# CT_v01.net
KiCad netlist of a schematic drawn in Altium Designer
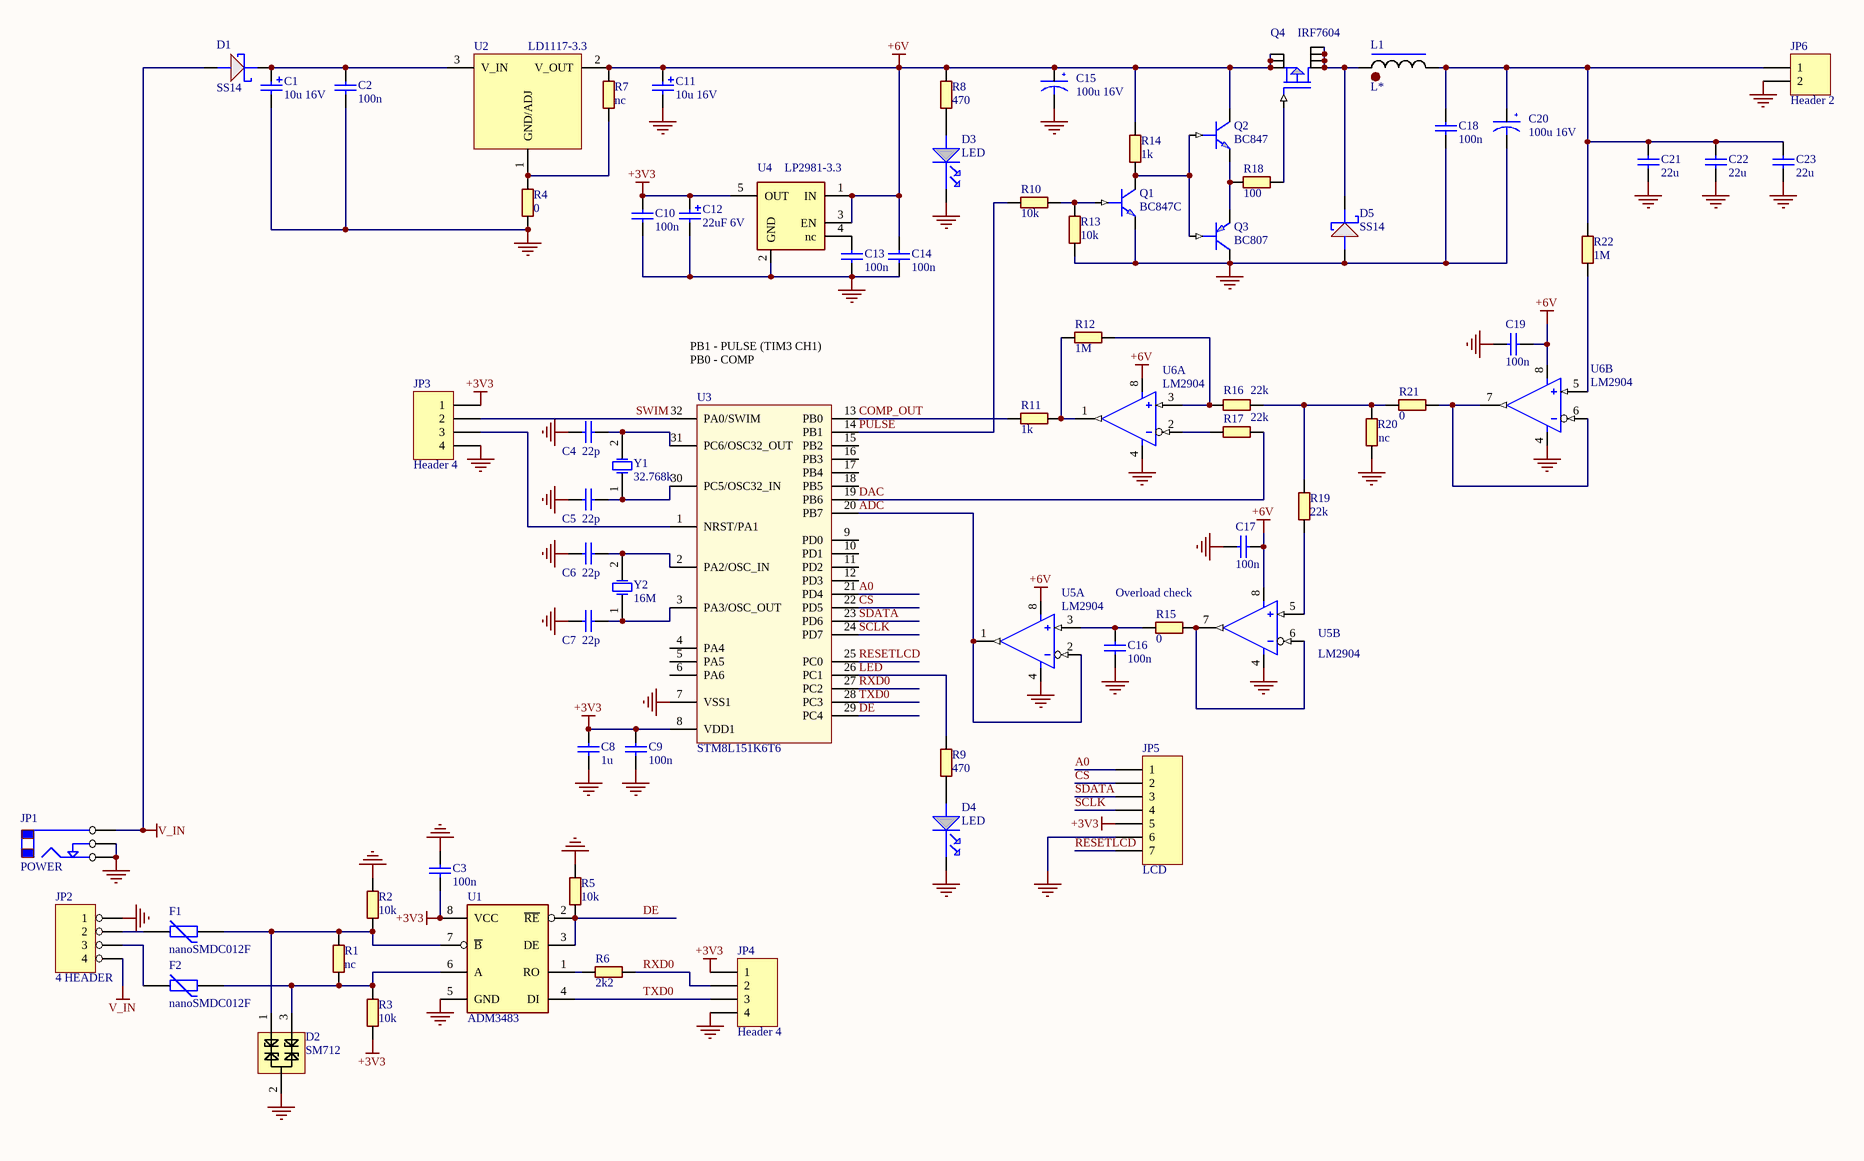
[diagram p0: CT_v01.SchDoc]

(export (version "E")
  (design (tool "Eeschema 10.0.6"))
  (components
    (comp (ref "C1") (value "10u 16V") (footprint "CAPMP3217X18N") (libsource (lib "Discrete") (part "CAPP")))
    (comp (ref "C2") (value "100n") (footprint "CAPC1608X08N") (libsource (lib "Discrete") (part "CAPN")))
    (comp (ref "C3") (value "100n") (footprint "CAPC1608X08N") (libsource (lib "Discrete") (part "CAPN")))
    (comp (ref "C4") (value "22p") (footprint "CAPC1608X08N") (libsource (lib "Discrete") (part "CAPN")))
    (comp (ref "C5") (value "22p") (footprint "CAPC1608X08N") (libsource (lib "Discrete") (part "CAPN")))
    (comp (ref "C6") (value "22p") (footprint "CAPC1608X08N") (libsource (lib "Discrete") (part "CAPN")))
    (comp (ref "C7") (value "22p") (footprint "CAPC1608X08N") (libsource (lib "Discrete") (part "CAPN")))
    (comp (ref "C8") (value "1u") (footprint "CAPC1608X08N") (libsource (lib "Discrete") (part "CAPN")))
    (comp (ref "C9") (value "100n") (footprint "CAPC1608X08N") (libsource (lib "Discrete") (part "CAPN")))
    (comp (ref "C10") (value "100n") (footprint "CAPC1608X08N") (libsource (lib "Discrete") (part "CAPN")))
    (comp (ref "C11")
      (value "10u 16V")
      (footprint "CAPMP3217X18N")
      (libsource (lib "Discrete") (part "CAPP"))
    )
    (comp (ref "C12")
      (value "22uF 6V")
      (footprint "CAPMP3217X18N")
      (libsource (lib "Discrete") (part "CAPP"))
    )
    (comp (ref "C13") (value "100n") (footprint "CAPC1608X08N") (libsource (lib "Discrete") (part "CAPN")))
    (comp (ref "C14") (value "100n") (footprint "CAPC1608X08N") (libsource (lib "Discrete") (part "CAPN")))
    (comp (ref "C15")
      (value "100u 16V")
      (footprint "CAPPRD200W50D600H1250")
      (libsource (lib "Discrete") (part "C-EL-DIP"))
    )
    (comp (ref "C16") (value "100n") (footprint "CAPC1608X08N") (libsource (lib "Discrete") (part "CAPN")))
    (comp (ref "C17") (value "100n") (footprint "CAPC1608X08N") (libsource (lib "Discrete") (part "CAPN")))
    (comp (ref "C18") (value "100n") (footprint "CAPC1608X08N") (libsource (lib "Discrete") (part "CAPN")))
    (comp (ref "C19") (value "100n") (footprint "CAPC1608X08N") (libsource (lib "Discrete") (part "CAPN")))
    (comp (ref "C20")
      (value "100u 16V")
      (footprint "CAPPRD200W50D600H1250")
      (libsource (lib "Discrete") (part "C-EL-DIP"))
    )
    (comp (ref "C21") (value "22u") (footprint "CAPC3216X14N") (libsource (lib "Discrete") (part "CAPN")))
    (comp (ref "C22") (value "22u") (footprint "CAPC3216X14N") (libsource (lib "Discrete") (part "CAPN")))
    (comp (ref "C23") (value "22u") (footprint "CAPC3216X14N") (libsource (lib "Discrete") (part "CAPN")))
    (comp (ref "D1")
      (value "SS14")
      (footprint "DIOM521X260X241L114X145N")
      (libsource (lib "Discrete") (part "DIODE SCHOTTKY"))
    )
    (comp (ref "D2") (value "SM712") (footprint "SOT-23") (libsource (lib "ul2016") (part "SM712")))
    (comp (ref "D3") (value "LED") (footprint "LEDC200X125X80L40N") (libsource (lib "Discrete") (part "LED")))
    (comp (ref "D4") (value "LED") (footprint "LEDC200X125X80L40N") (libsource (lib "Discrete") (part "LED")))
    (comp (ref "D5")
      (value "SS14")
      (footprint "DIOM521X260X241L114X145N")
      (libsource (lib "Discrete") (part "DIODE SCHOTTKY"))
    )
    (comp (ref "F1")
      (value "nanoSMDC012F")
      (footprint "RESC3216X07N")
      (libsource (lib "ul2016") (part "VARISTOR"))
    )
    (comp (ref "F2")
      (value "nanoSMDC012F")
      (footprint "RESC3216X07N")
      (libsource (lib "ul2016") (part "VARISTOR"))
    )
    (comp (ref "JP1")
      (value "POWER")
      (footprint "DC-140-003")
      (libsource (lib "Connectors$switces") (part "POWER"))
    )
    (comp (ref "JP2")
      (value "4 HEADER")
      (footprint "TERMINAL4")
      (description "4 Pin Header")
      (libsource (lib "Connectors$switces") (part "4 HEADER"))
    )
    (comp (ref "JP3")
      (value "Header 4")
      (footprint "HDRV4W70P254_4X1_889X254H754")
      (description "Header, 4-Pin")
      (fields (field (name "PUBLISHER") "Altium Limited"))
      (libsource (lib "") (part "Header 4_1"))
    )
    (comp (ref "JP4")
      (value "Header 4")
      (footprint "HDRV4W70P254_4X1_889X254H754")
      (description "Header, 4-Pin")
      (fields (field (name "PUBLISHER") "Altium Limited"))
      (libsource (lib "Miscellaneous Connectors") (part "Header 4"))
    )
    (comp (ref "JP5")
      (value "LCD")
      (footprint "HDRV7W70P254_7X1_1651X254H754")
      (description "Header, 7-Pin")
      (fields (field (name "PUBLISHER") "Altium Limited"))
      (libsource (lib "Miscellaneous Connectors") (part "Header 7"))
    )
    (comp (ref "JP6")
      (value "Header 2")
      (footprint "TERMINAL2")
      (description "Header, 2-Pin")
      (fields (field (name "PUBLISHER") "Altium Limited"))
      (libsource (lib "Miscellaneous Connectors") (part "Header 2"))
    )
    (comp (ref "L1") (value "L*") (footprint "SND-0705") (libsource (lib "Discrete") (part "L*")))
    (comp (ref "Q1")
      (value "BC847C")
      (footprint "SOT95P245X110-3N")
      (libsource (lib "Discrete") (part "NPN"))
    )
    (comp (ref "Q2") (value "BC847") (footprint "SOT95P245X110-3N") (libsource (lib "Discrete") (part "NPN")))
    (comp (ref "Q3") (value "BC807") (footprint "SOT95P245X110-3N") (libsource (lib "Discrete") (part "PNP")))
    (comp (ref "Q4")
      (value "IRF7604")
      (footprint "SOP8P65_300X490X110L53X30N")
      (libsource (lib "Discrete") (part "MOSFET_P_8pins"))
    )
    (comp (ref "R1") (value "nc") (footprint "RESC1608X06N") (libsource (lib "") (part "RES_1")))
    (comp (ref "R2") (value "10k") (footprint "RESC1608X06N") (libsource (lib "") (part "RES_2")))
    (comp (ref "R3") (value "10k") (footprint "RESC1608X06N") (libsource (lib "") (part "RES_1")))
    (comp (ref "R4") (value "0") (footprint "RESC1608X06N") (libsource (lib "") (part "RES_2")))
    (comp (ref "R5") (value "10k") (footprint "RESC1608X06N") (libsource (lib "") (part "RES_1")))
    (comp (ref "R6") (value "2k2") (footprint "RESC1608X06N") (libsource (lib "Discrete") (part "RES")))
    (comp (ref "R7") (value "nc") (footprint "RESC1608X06N") (libsource (lib "") (part "RES_2")))
    (comp (ref "R8") (value "470") (footprint "RESC1608X06N") (libsource (lib "") (part "RES_1")))
    (comp (ref "R9") (value "470") (footprint "RESC1608X06N") (libsource (lib "") (part "RES_1")))
    (comp (ref "R10") (value "10k") (footprint "RESC1608X06N") (libsource (lib "Discrete") (part "RES")))
    (comp (ref "R11") (value "1k") (footprint "RESC1608X06N") (libsource (lib "Discrete") (part "RES")))
    (comp (ref "R12") (value "1M") (footprint "RESC1608X06N") (libsource (lib "Discrete") (part "RES")))
    (comp (ref "R13") (value "10k") (footprint "RESC1608X06N") (libsource (lib "") (part "RES_1")))
    (comp (ref "R14") (value "1k") (footprint "RESC1608X06N") (libsource (lib "") (part "RES_2")))
    (comp (ref "R15") (value "0") (footprint "RESC1608X06N") (libsource (lib "Discrete") (part "RES")))
    (comp (ref "R16") (value "22k") (footprint "RESC1608X06N") (libsource (lib "Discrete") (part "RES")))
    (comp (ref "R17") (value "22k") (footprint "RESC1608X06N") (libsource (lib "Discrete") (part "RES")))
    (comp (ref "R18") (value "100") (footprint "RESC1608X06N") (libsource (lib "Discrete") (part "RES")))
    (comp (ref "R19") (value "22k") (footprint "RESC1608X06N") (libsource (lib "") (part "RES_1")))
    (comp (ref "R20") (value "nc") (footprint "RESC1608X06N") (libsource (lib "") (part "RES_1")))
    (comp (ref "R21") (value "0") (footprint "RESC1608X06N") (libsource (lib "Discrete") (part "RES")))
    (comp (ref "R22") (value "1M") (footprint "RESC1608X06N") (libsource (lib "") (part "RES_2")))
    (comp (ref "U1")
      (value "ADM3483")
      (footprint "SOIC127P600X175-8N")
      (libsource (lib "ICs") (part "SN65HVD12DG4"))
    )
    (comp (ref "U2")
      (value "LD1117-3.3")
      (footprint "SOT230P700X180-4N")
      (libsource (lib "RFM_PS_V01") (part "LM1117_3.3"))
    )
    (comp (ref "U3")
      (value "STM8L151K6T6")
      (footprint "TQFP80P900X900X160-32N")
      (libsource (lib "CT") (part "STM8L151K6T6"))
    )
    (comp (ref "U4")
      (value "LP2981-3.3")
      (footprint "SOT95P245X110-5N")
      (libsource (lib "ICs") (part "LP2981-3.3"))
    )
    (comp (ref "U5")
      (value "LM2904")
      (footprint "SOIC127P600X175-8N")
      (description "2 Operation amplifier")
      (libsource (lib "ICs") (part "LM2904"))
    )
    (comp (ref "U6")
      (value "LM2904")
      (footprint "SOIC127P600X175-8N")
      (description "2 Operation amplifier")
      (libsource (lib "ICs") (part "LM2904"))
    )
    (comp (ref "Y1")
      (value "32.768k")
      (footprint "KX26")
      (description "Crystal Oscillator")
      (fields (field (name "PUBLISHER") "Altium Limited"))
      (libsource (lib "Miscellaneous Devices") (part "XTAL"))
    )
    (comp (ref "Y2")
      (value "16M")
      (footprint "XTAL_HC49P488W43L1117T475H350")
      (description "Crystal Oscillator")
      (fields (field (name "PUBLISHER") "Altium Limited"))
      (libsource (lib "Miscellaneous Devices") (part "XTAL"))
    )
  )
  (nets
    (net (code "1") (name "+3V3") (class "Default")
      (node (ref "C10") (pin "1") (pinfunction "1_1") (pintype "passive"))
      (node (ref "C12") (pin "2") (pinfunction "2_2") (pintype "passive"))
      (node (ref "C3") (pin "2") (pinfunction "2_2") (pintype "passive"))
      (node (ref "C8") (pin "1") (pinfunction "1_1") (pintype "passive"))
      (node (ref "C9") (pin "1") (pinfunction "1_1") (pintype "passive"))
      (node (ref "JP3") (pin "1") (pinfunction "1_1") (pintype "passive"))
      (node (ref "JP4") (pin "1") (pinfunction "1_1") (pintype "passive"))
      (node (ref "JP5") (pin "5") (pinfunction "5_5") (pintype "passive"))
      (node (ref "R3") (pin "2") (pinfunction "2_2") (pintype "passive"))
      (node (ref "U1") (pin "8") (pinfunction "VCC_8") (pintype "passive"))
      (node (ref "U3") (pin "8") (pinfunction "VDD1_8") (pintype "passive"))
      (node (ref "U4") (pin "5") (pinfunction "OUT_5") (pintype "passive"))
    )
    (net (code "2") (name "+6V") (class "Default")
      (node (ref "C11") (pin "2") (pinfunction "2_2") (pintype "passive"))
      (node (ref "C14") (pin "1") (pinfunction "1_1") (pintype "passive"))
      (node (ref "C15") (pin "2") (pinfunction "+_2") (pintype "passive"))
      (node (ref "C17") (pin "2") (pinfunction "2_2") (pintype "passive"))
      (node (ref "C19") (pin "2") (pinfunction "2_2") (pintype "passive"))
      (node (ref "Q2") (pin "2") (pinfunction "COLLECTOR_2") (pintype "passive"))
      (node (ref "Q4") (pin "1") (pinfunction "SOURCE_1") (pintype "passive"))
      (node (ref "Q4") (pin "2") (pinfunction "SOURCE_2") (pintype "passive"))
      (node (ref "Q4") (pin "3") (pinfunction "SOURCE_3") (pintype "passive"))
      (node (ref "R14") (pin "2") (pinfunction "2_2") (pintype "passive"))
      (node (ref "R7") (pin "2") (pinfunction "2_2") (pintype "passive"))
      (node (ref "R8") (pin "1") (pinfunction "1_1") (pintype "passive"))
      (node (ref "U2") (pin "2") (pinfunction "V_OUT_2") (pintype "passive"))
      (node (ref "U4") (pin "1") (pinfunction "IN_1") (pintype "passive"))
      (node (ref "U4") (pin "3") (pinfunction "EN_3") (pintype "passive"))
      (node (ref "U5") (pin "8") (pinfunction "V+_8") (pintype "passive"))
      (node (ref "U6") (pin "8") (pinfunction "V+_8") (pintype "passive"))
    )
    (net (code "3") (name "/A0") (class "Default")
      (node (ref "JP5") (pin "1") (pinfunction "1_1") (pintype "passive"))
      (node (ref "U3") (pin "21") (pinfunction "PD4_21") (pintype "passive"))
    )
    (net (code "4") (name "/ADC") (class "Default")
      (node (ref "U3") (pin "20") (pinfunction "PB7_20") (pintype "passive"))
      (node (ref "U5") (pin "1") (pinfunction "OUT_1") (pintype "output"))
      (node (ref "U5") (pin "2") (pinfunction "-IN_2") (pintype "input"))
    )
    (net (code "5") (name "/COMP_OUT") (class "Default")
      (node (ref "R11") (pin "2") (pinfunction "2_2") (pintype "passive"))
      (node (ref "U3") (pin "13") (pinfunction "PB0_13") (pintype "passive"))
    )
    (net (code "6") (name "/CS") (class "Default")
      (node (ref "JP5") (pin "2") (pinfunction "2_2") (pintype "passive"))
      (node (ref "U3") (pin "22") (pinfunction "PD5_22") (pintype "passive"))
    )
    (net (code "7") (name "/DAC") (class "Default")
      (node (ref "R17") (pin "1") (pinfunction "1_1") (pintype "passive"))
      (node (ref "U3") (pin "19") (pinfunction "PB6_19") (pintype "passive"))
    )
    (net (code "8") (name "/DE") (class "Default")
      (node (ref "R5") (pin "2") (pinfunction "2_2") (pintype "passive"))
      (node (ref "U1") (pin "2") (pinfunction "~{RE}_2") (pintype "passive"))
      (node (ref "U1") (pin "3") (pinfunction "DE_3") (pintype "passive"))
      (node (ref "U3") (pin "29") (pinfunction "PC4_29") (pintype "passive"))
    )
    (net (code "9") (name "/LED") (class "Default")
      (node (ref "R9") (pin "1") (pinfunction "1_1") (pintype "passive"))
      (node (ref "U3") (pin "26") (pinfunction "PC1_26") (pintype "passive"))
    )
    (net (code "10") (name "/PULSE") (class "Default")
      (node (ref "R10") (pin "2") (pinfunction "2_2") (pintype "passive"))
      (node (ref "U3") (pin "14") (pinfunction "PB1_14") (pintype "passive"))
    )
    (net (code "11") (name "/RESETLCD") (class "Default")
      (node (ref "JP5") (pin "7") (pinfunction "7_7") (pintype "passive"))
      (node (ref "U3") (pin "25") (pinfunction "PC0_25") (pintype "passive"))
    )
    (net (code "12") (name "/RXD0") (class "Default")
      (node (ref "JP4") (pin "2") (pinfunction "2_2") (pintype "passive"))
      (node (ref "R6") (pin "1") (pinfunction "1_1") (pintype "passive"))
      (node (ref "U3") (pin "27") (pinfunction "PC2_27") (pintype "passive"))
    )
    (net (code "13") (name "/SCLK") (class "Default")
      (node (ref "JP5") (pin "4") (pinfunction "4_4") (pintype "passive"))
      (node (ref "U3") (pin "24") (pinfunction "PD7_24") (pintype "passive"))
    )
    (net (code "14") (name "/SDATA") (class "Default")
      (node (ref "JP5") (pin "3") (pinfunction "3_3") (pintype "passive"))
      (node (ref "U3") (pin "23") (pinfunction "PD6_23") (pintype "passive"))
    )
    (net (code "15") (name "/SWIM") (class "Default")
      (node (ref "JP3") (pin "2") (pinfunction "2_2") (pintype "passive"))
      (node (ref "U3") (pin "32") (pinfunction "PA0/SWIM_32") (pintype "passive"))
    )
    (net (code "16") (name "/TXD0") (class "Default")
      (node (ref "JP4") (pin "3") (pinfunction "3_3") (pintype "passive"))
      (node (ref "U1") (pin "4") (pinfunction "DI_4") (pintype "passive"))
      (node (ref "U3") (pin "28") (pinfunction "PC3_28") (pintype "passive"))
    )
    (net (code "17") (name "GND") (class "Default")
      (node (ref "C1") (pin "1") (pinfunction "1_1") (pintype "passive"))
      (node (ref "C10") (pin "2") (pinfunction "2_2") (pintype "passive"))
      (node (ref "C11") (pin "1") (pinfunction "1_1") (pintype "passive"))
      (node (ref "C12") (pin "1") (pinfunction "1_1") (pintype "passive"))
      (node (ref "C13") (pin "2") (pinfunction "2_2") (pintype "passive"))
      (node (ref "C14") (pin "2") (pinfunction "2_2") (pintype "passive"))
      (node (ref "C15") (pin "1") (pinfunction "-_1") (pintype "passive"))
      (node (ref "C16") (pin "2") (pinfunction "2_2") (pintype "passive"))
      (node (ref "C17") (pin "1") (pinfunction "1_1") (pintype "passive"))
      (node (ref "C18") (pin "2") (pinfunction "2_2") (pintype "passive"))
      (node (ref "C19") (pin "1") (pinfunction "1_1") (pintype "passive"))
      (node (ref "C2") (pin "2") (pinfunction "2_2") (pintype "passive"))
      (node (ref "C20") (pin "1") (pinfunction "-_1") (pintype "passive"))
      (node (ref "C21") (pin "2") (pinfunction "2_2") (pintype "passive"))
      (node (ref "C22") (pin "2") (pinfunction "2_2") (pintype "passive"))
      (node (ref "C23") (pin "2") (pinfunction "2_2") (pintype "passive"))
      (node (ref "C3") (pin "1") (pinfunction "1_1") (pintype "passive"))
      (node (ref "C4") (pin "1") (pinfunction "1_1") (pintype "passive"))
      (node (ref "C5") (pin "1") (pinfunction "1_1") (pintype "passive"))
      (node (ref "C6") (pin "1") (pinfunction "1_1") (pintype "passive"))
      (node (ref "C7") (pin "1") (pinfunction "1_1") (pintype "passive"))
      (node (ref "C8") (pin "2") (pinfunction "2_2") (pintype "passive"))
      (node (ref "C9") (pin "2") (pinfunction "2_2") (pintype "passive"))
      (node (ref "D2") (pin "2") (pinfunction "2_2") (pintype "passive"))
      (node (ref "D3") (pin "K") (pinfunction "CATHODE_K") (pintype "passive"))
      (node (ref "D4") (pin "K") (pinfunction "CATHODE_K") (pintype "passive"))
      (node (ref "D5") (pin "A") (pinfunction "A_A") (pintype "passive"))
      (node (ref "JP1") (pin "2") (pinfunction "C_2") (pintype "passive"))
      (node (ref "JP1") (pin "3") (pinfunction "B_3") (pintype "passive"))
      (node (ref "JP2") (pin "1") (pinfunction "1_1") (pintype "passive"))
      (node (ref "JP3") (pin "4") (pinfunction "4_4") (pintype "passive"))
      (node (ref "JP4") (pin "4") (pinfunction "4_4") (pintype "passive"))
      (node (ref "JP5") (pin "6") (pinfunction "6_6") (pintype "passive"))
      (node (ref "JP6") (pin "2") (pinfunction "2_2") (pintype "passive"))
      (node (ref "Q1") (pin "3") (pinfunction "EMITTER_3") (pintype "passive"))
      (node (ref "Q3") (pin "2") (pinfunction "COLLECTOR_2") (pintype "passive"))
      (node (ref "R13") (pin "2") (pinfunction "2_2") (pintype "passive"))
      (node (ref "R2") (pin "2") (pinfunction "2_2") (pintype "passive"))
      (node (ref "R20") (pin "2") (pinfunction "2_2") (pintype "passive"))
      (node (ref "R4") (pin "1") (pinfunction "1_1") (pintype "passive"))
      (node (ref "R5") (pin "1") (pinfunction "1_1") (pintype "passive"))
      (node (ref "U1") (pin "5") (pinfunction "GND_5") (pintype "passive"))
      (node (ref "U3") (pin "7") (pinfunction "VSS1_7") (pintype "passive"))
      (node (ref "U4") (pin "2") (pinfunction "GND_2") (pintype "passive"))
      (node (ref "U5") (pin "4") (pinfunction "V-_4") (pintype "passive"))
      (node (ref "U6") (pin "4") (pinfunction "V-_4") (pintype "passive"))
    )
    (net (code "18") (name "Net-(C20-+)") (class "Default")
      (node (ref "C18") (pin "1") (pinfunction "1_1") (pintype "passive"))
      (node (ref "C20") (pin "2") (pinfunction "+_2") (pintype "passive"))
      (node (ref "C21") (pin "1") (pinfunction "1_1") (pintype "passive"))
      (node (ref "C22") (pin "1") (pinfunction "1_1") (pintype "passive"))
      (node (ref "C23") (pin "1") (pinfunction "1_1") (pintype "passive"))
      (node (ref "JP6") (pin "1") (pinfunction "1_1") (pintype "passive"))
      (node (ref "L1") (pin "2") (pinfunction "2_2") (pintype "passive"))
      (node (ref "R22") (pin "2") (pinfunction "2_2") (pintype "passive"))
    )
    (net (code "19") (name "Net-(D3-ANODE)") (class "Default")
      (node (ref "D3") (pin "A") (pinfunction "ANODE_A") (pintype "passive"))
      (node (ref "R8") (pin "2") (pinfunction "2_2") (pintype "passive"))
    )
    (net (code "20") (name "Net-(D4-ANODE)") (class "Default")
      (node (ref "D4") (pin "A") (pinfunction "ANODE_A") (pintype "passive"))
      (node (ref "R9") (pin "2") (pinfunction "2_2") (pintype "passive"))
    )
    (net (code "21") (name "Net-(D5-PadK)") (class "Default")
      (node (ref "D5") (pin "K") (pinfunction "K_K") (pintype "passive"))
      (node (ref "L1") (pin "1") (pinfunction "1_1") (pintype "passive"))
      (node (ref "Q4") (pin "5") (pinfunction "DRAIN_5") (pintype "passive"))
      (node (ref "Q4") (pin "6") (pinfunction "DRAIN_6") (pintype "passive"))
      (node (ref "Q4") (pin "7") (pinfunction "DRAIN_7") (pintype "passive"))
      (node (ref "Q4") (pin "8") (pinfunction "DRAIN_8") (pintype "passive"))
    )
    (net (code "22") (name "Net-(F1-Pad1)") (class "Default")
      (node (ref "F1") (pin "1") (pinfunction "1_1") (pintype "passive"))
      (node (ref "JP2") (pin "2") (pinfunction "2_2") (pintype "passive"))
    )
    (net (code "23") (name "Net-(F2-Pad1)") (class "Default")
      (node (ref "F2") (pin "1") (pinfunction "1_1") (pintype "passive"))
      (node (ref "JP2") (pin "3") (pinfunction "3_3") (pintype "passive"))
    )
    (net (code "24") (name "Net-(Q1-BASE)") (class "Default")
      (node (ref "Q1") (pin "1") (pinfunction "BASE_1") (pintype "input"))
      (node (ref "R10") (pin "1") (pinfunction "1_1") (pintype "passive"))
      (node (ref "R13") (pin "1") (pinfunction "1_1") (pintype "passive"))
    )
    (net (code "25") (name "Net-(Q1-COLLECTOR)") (class "Default")
      (node (ref "Q1") (pin "2") (pinfunction "COLLECTOR_2") (pintype "passive"))
      (node (ref "Q2") (pin "1") (pinfunction "BASE_1") (pintype "input"))
      (node (ref "Q3") (pin "1") (pinfunction "BASE_1") (pintype "input"))
      (node (ref "R14") (pin "1") (pinfunction "1_1") (pintype "passive"))
    )
    (net (code "26") (name "Net-(Q2-EMITTER)") (class "Default")
      (node (ref "Q2") (pin "3") (pinfunction "EMITTER_3") (pintype "passive"))
      (node (ref "Q3") (pin "3") (pinfunction "EMITTER_3") (pintype "passive"))
      (node (ref "R18") (pin "2") (pinfunction "2_2") (pintype "passive"))
    )
    (net (code "27") (name "Net-(Q4-GATE)") (class "Default")
      (node (ref "Q4") (pin "4") (pinfunction "GATE_4") (pintype "input"))
      (node (ref "R18") (pin "1") (pinfunction "1_1") (pintype "passive"))
    )
    (net (code "28") (name "Net-(R16-Pad1)") (class "Default")
      (node (ref "R16") (pin "1") (pinfunction "1_1") (pintype "passive"))
      (node (ref "R19") (pin "1") (pinfunction "1_1") (pintype "passive"))
      (node (ref "R20") (pin "1") (pinfunction "1_1") (pintype "passive"))
      (node (ref "R21") (pin "2") (pinfunction "2_2") (pintype "passive"))
    )
    (net (code "29") (name "Net-(U1-A)") (class "Default")
      (node (ref "D2") (pin "3") (pinfunction "3_3") (pintype "passive"))
      (node (ref "F2") (pin "2") (pinfunction "2_2") (pintype "passive"))
      (node (ref "R1") (pin "2") (pinfunction "2_2") (pintype "passive"))
      (node (ref "R3") (pin "1") (pinfunction "1_1") (pintype "passive"))
      (node (ref "U1") (pin "6") (pinfunction "A_6") (pintype "passive"))
    )
    (net (code "30") (name "Net-(U1-RO)") (class "Default")
      (node (ref "R6") (pin "2") (pinfunction "2_2") (pintype "passive"))
      (node (ref "U1") (pin "1") (pinfunction "RO_1") (pintype "passive"))
    )
    (net (code "31") (name "Net-(U1-~{B})") (class "Default")
      (node (ref "D2") (pin "1") (pinfunction "1_1") (pintype "passive"))
      (node (ref "F1") (pin "2") (pinfunction "2_2") (pintype "passive"))
      (node (ref "R1") (pin "1") (pinfunction "1_1") (pintype "passive"))
      (node (ref "R2") (pin "1") (pinfunction "1_1") (pintype "passive"))
      (node (ref "U1") (pin "7") (pinfunction "~{B}_7") (pintype "passive"))
    )
    (net (code "32") (name "Net-(U2-GND{slash}ADJ)") (class "Default")
      (node (ref "R4") (pin "2") (pinfunction "2_2") (pintype "passive"))
      (node (ref "R7") (pin "1") (pinfunction "1_1") (pintype "passive"))
      (node (ref "U2") (pin "1") (pinfunction "GND/ADJ_1") (pintype "passive"))
    )
    (net (code "33") (name "Net-(U2-V_IN)") (class "Default")
      (node (ref "C1") (pin "2") (pinfunction "2_2") (pintype "passive"))
      (node (ref "C2") (pin "1") (pinfunction "1_1") (pintype "passive"))
      (node (ref "D1") (pin "K") (pinfunction "K_K") (pintype "passive"))
      (node (ref "U2") (pin "3") (pinfunction "V_IN_3") (pintype "passive"))
    )
    (net (code "34") (name "Net-(U3-NRST{slash}PA1)") (class "Default")
      (node (ref "JP3") (pin "3") (pinfunction "3_3") (pintype "passive"))
      (node (ref "U3") (pin "1") (pinfunction "NRST/PA1_1") (pintype "passive"))
    )
    (net (code "35") (name "Net-(U3-PA2{slash}OSC_IN)") (class "Default")
      (node (ref "C6") (pin "2") (pinfunction "2_2") (pintype "passive"))
      (node (ref "U3") (pin "2") (pinfunction "PA2/OSC_IN_2") (pintype "passive"))
      (node (ref "Y2") (pin "2") (pinfunction "OSC2_2") (pintype "passive"))
    )
    (net (code "36") (name "Net-(U3-PA3{slash}OSC_OUT)") (class "Default")
      (node (ref "C7") (pin "2") (pinfunction "2_2") (pintype "passive"))
      (node (ref "U3") (pin "3") (pinfunction "PA3/OSC_OUT_3") (pintype "passive"))
      (node (ref "Y2") (pin "1") (pinfunction "OSC1_1") (pintype "passive"))
    )
    (net (code "37") (name "Net-(U3-PC5{slash}OSC32_IN)") (class "Default")
      (node (ref "C5") (pin "2") (pinfunction "2_2") (pintype "passive"))
      (node (ref "U3") (pin "30") (pinfunction "PC5/OSC32_IN_30") (pintype "passive"))
      (node (ref "Y1") (pin "1") (pinfunction "OSC1_1") (pintype "passive"))
    )
    (net (code "38") (name "Net-(U3-PC6{slash}OSC32_OUT)") (class "Default")
      (node (ref "C4") (pin "2") (pinfunction "2_2") (pintype "passive"))
      (node (ref "U3") (pin "31") (pinfunction "PC6/OSC32_OUT_31") (pintype "passive"))
      (node (ref "Y1") (pin "2") (pinfunction "OSC2_2") (pintype "passive"))
    )
    (net (code "39") (name "Net-(U4-nc)") (class "Default")
      (node (ref "C13") (pin "1") (pinfunction "1_1") (pintype "passive"))
      (node (ref "U4") (pin "4") (pinfunction "nc_4") (pintype "passive"))
    )
    (net (code "40") (name "Net-(U5A-+IN)") (class "Default")
      (node (ref "C16") (pin "1") (pinfunction "1_1") (pintype "passive"))
      (node (ref "R15") (pin "2") (pinfunction "2_2") (pintype "passive"))
      (node (ref "U5") (pin "3") (pinfunction "+IN_3") (pintype "input"))
    )
    (net (code "41") (name "Net-(U5B-+IN)") (class "Default")
      (node (ref "R19") (pin "2") (pinfunction "2_2") (pintype "passive"))
      (node (ref "U5") (pin "5") (pinfunction "+IN_5") (pintype "input"))
    )
    (net (code "42") (name "Net-(U5B--IN)") (class "Default")
      (node (ref "R15") (pin "1") (pinfunction "1_1") (pintype "passive"))
      (node (ref "U5") (pin "6") (pinfunction "-IN_6") (pintype "input"))
      (node (ref "U5") (pin "7") (pinfunction "OUT_7") (pintype "output"))
    )
    (net (code "43") (name "Net-(U6A-+IN)") (class "Default")
      (node (ref "R12") (pin "1") (pinfunction "1_1") (pintype "passive"))
      (node (ref "R16") (pin "2") (pinfunction "2_2") (pintype "passive"))
      (node (ref "U6") (pin "3") (pinfunction "+IN_3") (pintype "input"))
    )
    (net (code "44") (name "Net-(U6A--IN)") (class "Default")
      (node (ref "R17") (pin "2") (pinfunction "2_2") (pintype "passive"))
      (node (ref "U6") (pin "2") (pinfunction "-IN_2") (pintype "input"))
    )
    (net (code "45") (name "Net-(U6A-OUT)") (class "Default")
      (node (ref "R11") (pin "1") (pinfunction "1_1") (pintype "passive"))
      (node (ref "R12") (pin "2") (pinfunction "2_2") (pintype "passive"))
      (node (ref "U6") (pin "1") (pinfunction "OUT_1") (pintype "output"))
    )
    (net (code "46") (name "Net-(U6B-+IN)") (class "Default")
      (node (ref "R22") (pin "1") (pinfunction "1_1") (pintype "passive"))
      (node (ref "U6") (pin "5") (pinfunction "+IN_5") (pintype "input"))
    )
    (net (code "47") (name "Net-(U6B--IN)") (class "Default")
      (node (ref "R21") (pin "1") (pinfunction "1_1") (pintype "passive"))
      (node (ref "U6") (pin "6") (pinfunction "-IN_6") (pintype "input"))
      (node (ref "U6") (pin "7") (pinfunction "OUT_7") (pintype "output"))
    )
    (net (code "48") (name "V_IN") (class "Default")
      (node (ref "D1") (pin "A") (pinfunction "A_A") (pintype "passive"))
      (node (ref "JP1") (pin "1") (pinfunction "A_1") (pintype "passive"))
      (node (ref "JP2") (pin "4") (pinfunction "4_4") (pintype "passive"))
    )
    (net (code "49") (name "unconnected-(U3-PA4-Pad4)") (class "Default")
      (node (ref "U3") (pin "4") (pinfunction "PA4_4") (pintype "passive"))
    )
    (net (code "50") (name "unconnected-(U3-PA5-Pad5)") (class "Default")
      (node (ref "U3") (pin "5") (pinfunction "PA5_5") (pintype "passive"))
    )
    (net (code "51") (name "unconnected-(U3-PA6-Pad6)") (class "Default")
      (node (ref "U3") (pin "6") (pinfunction "PA6_6") (pintype "passive"))
    )
    (net (code "52") (name "unconnected-(U3-PB2-Pad15)") (class "Default")
      (node (ref "U3") (pin "15") (pinfunction "PB2_15") (pintype "passive"))
    )
    (net (code "53") (name "unconnected-(U3-PB3-Pad16)") (class "Default")
      (node (ref "U3") (pin "16") (pinfunction "PB3_16") (pintype "passive"))
    )
    (net (code "54") (name "unconnected-(U3-PB4-Pad17)") (class "Default")
      (node (ref "U3") (pin "17") (pinfunction "PB4_17") (pintype "passive"))
    )
    (net (code "55") (name "unconnected-(U3-PB5-Pad18)") (class "Default")
      (node (ref "U3") (pin "18") (pinfunction "PB5_18") (pintype "passive"))
    )
    (net (code "56") (name "unconnected-(U3-PD0-Pad9)") (class "Default")
      (node (ref "U3") (pin "9") (pinfunction "PD0_9") (pintype "passive"))
    )
    (net (code "57") (name "unconnected-(U3-PD1-Pad10)") (class "Default")
      (node (ref "U3") (pin "10") (pinfunction "PD1_10") (pintype "passive"))
    )
    (net (code "58") (name "unconnected-(U3-PD2-Pad11)") (class "Default")
      (node (ref "U3") (pin "11") (pinfunction "PD2_11") (pintype "passive"))
    )
    (net (code "59") (name "unconnected-(U3-PD3-Pad12)") (class "Default")
      (node (ref "U3") (pin "12") (pinfunction "PD3_12") (pintype "passive"))
    )
  )
)
